# FEE_v0_3.net
KiCad netlist of a schematic drawn in EAGLE
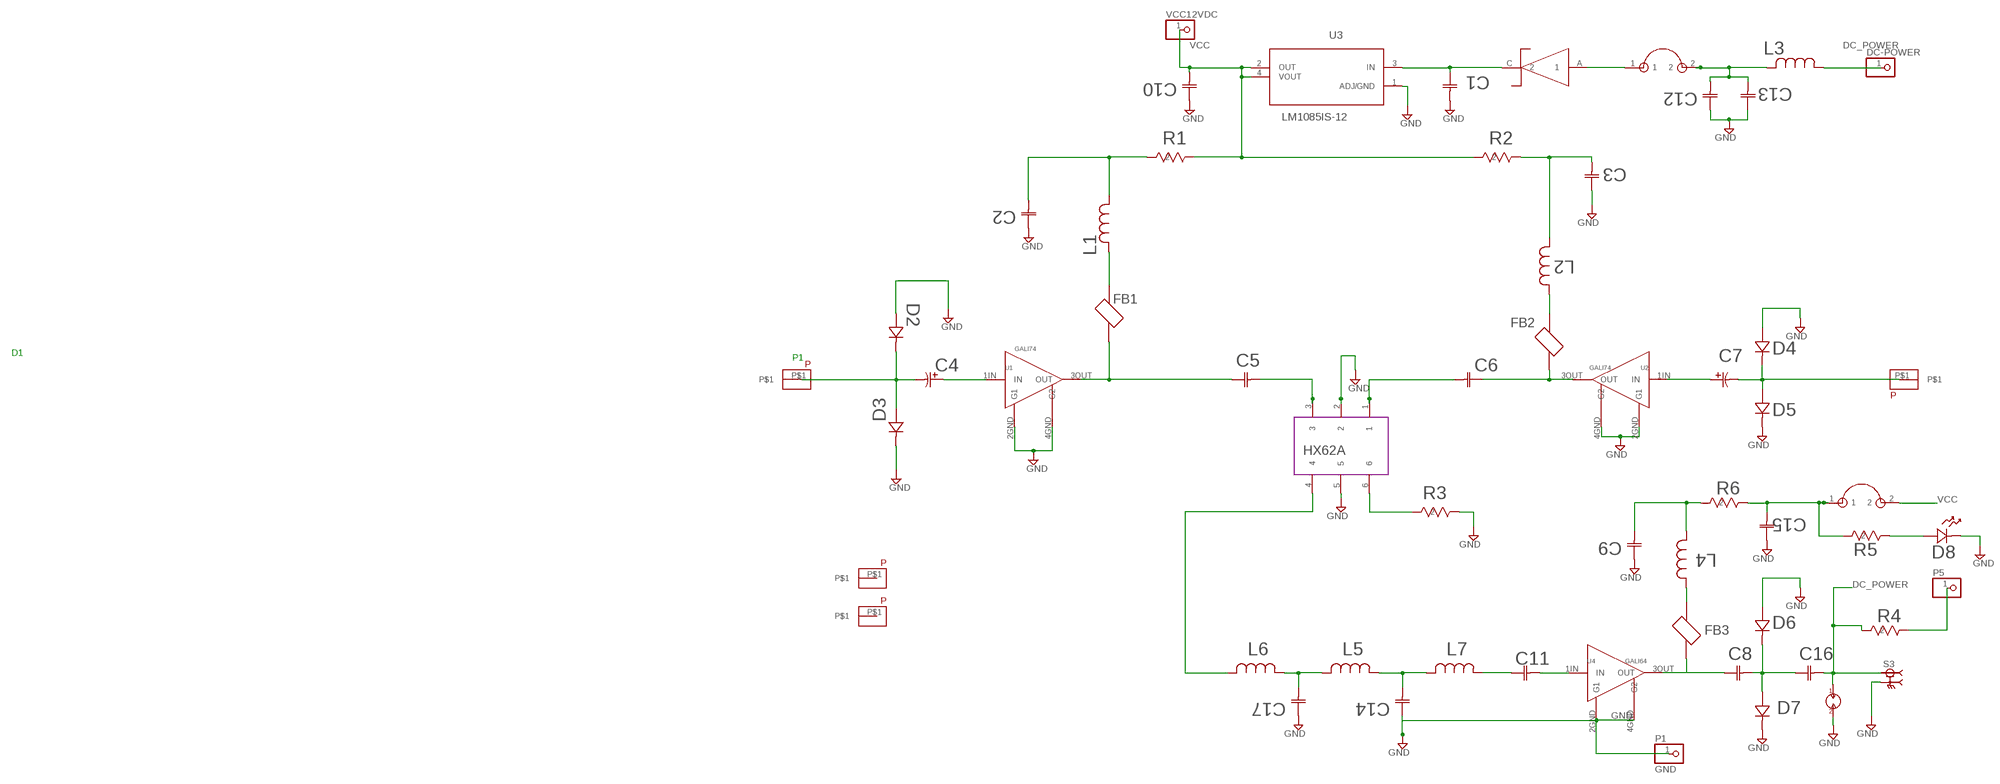
[diagram p0: schematic, sheet 1]

(export (version "E")
  (design (tool "Eeschema 10.0.6"))
  (components
    (comp (ref "C1")
      (value "F931E106MCC")
      (footprint "eagle-import:F93-C_AVX")
      (fields (field (name "COPYRIGHT") "Copyright (C) 2018 Accelerated Designs. All rights reserved"))
      (libsource (lib "eagle-import") (part "F931E106MCC"))
    )
    (comp (ref "C2")
      (value "C1206C104G5JAC7800")
      (footprint "eagle-import:CAPC340180_135N_KEM")
      (libsource (lib "eagle-import") (part "C1206C104G5JAC7800"))
    )
    (comp (ref "C3")
      (value "C1206C104G5JAC7800")
      (footprint "eagle-import:CAPC340180_135N_KEM")
      (libsource (lib "eagle-import") (part "C1206C104G5JAC7800"))
    )
    (comp (ref "C4")
      (value "ECJ-3FB2J102K")
      (footprint "eagle-import:CC1206_3_PAN")
      (libsource (lib "eagle-import") (part "ECJ-3FB2J102K"))
    )
    (comp (ref "C5")
      (value "C1206C104G5JAC7800")
      (footprint "eagle-import:CAPC340180_135N_KEM")
      (libsource (lib "eagle-import") (part "C1206C104G5JAC7800"))
    )
    (comp (ref "C6")
      (value "C1206C104G5JAC7800")
      (footprint "eagle-import:CAPC340180_135N_KEM")
      (libsource (lib "eagle-import") (part "C1206C104G5JAC7800"))
    )
    (comp (ref "C7")
      (value "ECJ-3FB2J102K")
      (footprint "eagle-import:CC1206_3_PAN")
      (libsource (lib "eagle-import") (part "ECJ-3FB2J102K"))
    )
    (comp (ref "C8")
      (value "C1206C104G5JAC7800")
      (footprint "eagle-import:CAPC340180_135N_KEM")
      (libsource (lib "eagle-import") (part "C1206C104G5JAC7800"))
    )
    (comp (ref "C9")
      (value "C1206C104G5JAC7800")
      (footprint "eagle-import:CAPC340180_135N_KEM")
      (libsource (lib "eagle-import") (part "C1206C104G5JAC7800"))
    )
    (comp (ref "C10")
      (value "F931E106MCC")
      (footprint "eagle-import:F93-C_AVX")
      (fields (field (name "COPYRIGHT") "Copyright (C) 2018 Accelerated Designs. All rights reserved"))
      (libsource (lib "eagle-import") (part "F931E106MCC"))
    )
    (comp (ref "C11")
      (value "C1206C104G5JAC7800")
      (footprint "eagle-import:CAPC340180_135N_KEM")
      (libsource (lib "eagle-import") (part "C1206C104G5JAC7800"))
    )
    (comp (ref "C12")
      (value "C1206C104G5JAC7800")
      (footprint "eagle-import:CAPC340180_135N_KEM")
      (libsource (lib "eagle-import") (part "C1206C104G5JAC7800"))
    )
    (comp (ref "C13")
      (value "C1206C104G5JAC7800")
      (footprint "eagle-import:CAPC340180_135N_KEM")
      (libsource (lib "eagle-import") (part "C1206C104G5JAC7800"))
    )
    (comp (ref "C14")
      (value "06031A330GAT2A")
      (footprint "eagle-import:CAP_0603G_AVX")
      (fields (field (name "COPYRIGHT") "Copyright (C) 2018 Accelerated Designs. All rights reserved"))
      (libsource (lib "eagle-import") (part "06031A330GAT2A"))
    )
    (comp (ref "C15")
      (value "C1206C104G5JAC7800")
      (footprint "eagle-import:CAPC340180_135N_KEM")
      (libsource (lib "eagle-import") (part "C1206C104G5JAC7800"))
    )
    (comp (ref "C16")
      (value "C1206C104G5JAC7800")
      (footprint "eagle-import:CAPC340180_135N_KEM")
      (libsource (lib "eagle-import") (part "C1206C104G5JAC7800"))
    )
    (comp (ref "C17")
      (value "06031A330GAT2A")
      (footprint "eagle-import:CAP_0603G_AVX")
      (fields (field (name "COPYRIGHT") "Copyright (C) 2018 Accelerated Designs. All rights reserved"))
      (libsource (lib "eagle-import") (part "06031A330GAT2A"))
    )
    (comp (ref "D1")
      (value "DIOM5436X247N")
      (footprint "eagle-import:DIOM5436X247N")
      (libsource (lib "eagle-import") (part "DIOM5436X247N"))
    )
    (comp (ref "D2")
      (value "1N4148WX-TP")
      (footprint "eagle-import:CR_SOD323_MCC")
      (fields (field (name "COPYRIGHT") "Copyright (C) 2018 Accelerated Designs. All rights reserved"))
      (libsource (lib "eagle-import") (part "1N4148WX-TP"))
    )
    (comp (ref "D3")
      (value "1N4148WX-TP")
      (footprint "eagle-import:CR_SOD323_MCC")
      (fields (field (name "COPYRIGHT") "Copyright (C) 2018 Accelerated Designs. All rights reserved"))
      (libsource (lib "eagle-import") (part "1N4148WX-TP"))
    )
    (comp (ref "D4")
      (value "1N4148WX-TP")
      (footprint "eagle-import:CR_SOD323_MCC")
      (fields (field (name "COPYRIGHT") "Copyright (C) 2018 Accelerated Designs. All rights reserved"))
      (libsource (lib "eagle-import") (part "1N4148WX-TP"))
    )
    (comp (ref "D5")
      (value "1N4148WX-TP")
      (footprint "eagle-import:CR_SOD323_MCC")
      (fields (field (name "COPYRIGHT") "Copyright (C) 2018 Accelerated Designs. All rights reserved"))
      (libsource (lib "eagle-import") (part "1N4148WX-TP"))
    )
    (comp (ref "D6")
      (value "1N4148WX-TP")
      (footprint "eagle-import:CR_SOD323_MCC")
      (fields (field (name "COPYRIGHT") "Copyright (C) 2018 Accelerated Designs. All rights reserved"))
      (libsource (lib "eagle-import") (part "1N4148WX-TP"))
    )
    (comp (ref "D7")
      (value "1N4148WX-TP")
      (footprint "eagle-import:CR_SOD323_MCC")
      (fields (field (name "COPYRIGHT") "Copyright (C) 2018 Accelerated Designs. All rights reserved"))
      (libsource (lib "eagle-import") (part "1N4148WX-TP"))
    )
    (comp (ref "D8")
      (value "SML-LX1206SIC-TR")
      (footprint "eagle-import:LED_SML-LX1206SIC-TR_LUM")
      (fields (field (name "COPYRIGHT") "Copyright (C) 2018 Accelerated Designs. All rights reserved"))
      (libsource (lib "eagle-import") (part "SML-LX1206SIC-TR"))
    )
    (comp (ref "DC-POWER")
      (value "PINHD-1X1")
      (footprint "eagle-import:1X01")
      (libsource (lib "eagle-import") (part "PINHD-1X1"))
    )
    (comp (ref "FB1")
      (value "HZ0805C202R-10")
      (footprint "eagle-import:FB_HZ0805C202R-10")
      (fields
        (field (name "DIGI-KEY_PART_NUMBER") "240-2396-1-ND")
        (field (name "MF") "Laird-Signal Integrity")
      )
      (libsource (lib "eagle-import") (part "HZ0805C202R-10"))
    )
    (comp (ref "FB2")
      (value "HZ0805C202R-10")
      (footprint "eagle-import:FB_HZ0805C202R-10")
      (fields
        (field (name "DIGI-KEY_PART_NUMBER") "240-2396-1-ND")
        (field (name "MF") "Laird-Signal Integrity")
      )
      (libsource (lib "eagle-import") (part "HZ0805C202R-10"))
    )
    (comp (ref "FB3")
      (value "HZ0805C202R-10")
      (footprint "eagle-import:FB_HZ0805C202R-10")
      (fields
        (field (name "DIGI-KEY_PART_NUMBER") "240-2396-1-ND")
        (field (name "MF") "Laird-Signal Integrity")
      )
      (libsource (lib "eagle-import") (part "HZ0805C202R-10"))
    )
    (comp (ref "L1")
      (value "AISC-1008-4R7J-T")
      (footprint "eagle-import:AISC-1008_ABR")
      (libsource (lib "eagle-import") (part "AISC-1008-4R7J-T"))
    )
    (comp (ref "L2")
      (value "AISC-1008-4R7J-T")
      (footprint "eagle-import:AISC-1008_ABR")
      (libsource (lib "eagle-import") (part "AISC-1008-4R7J-T"))
    )
    (comp (ref "L3")
      (value "AISC-1008-4R7J-T")
      (footprint "eagle-import:AISC-1008_ABR")
      (libsource (lib "eagle-import") (part "AISC-1008-4R7J-T"))
    )
    (comp (ref "L4")
      (value "AISC-1008-4R7J-T")
      (footprint "eagle-import:AISC-1008_ABR")
      (libsource (lib "eagle-import") (part "AISC-1008-4R7J-T"))
    )
    (comp (ref "L5")
      (value "AISC-1008-4R7J-T")
      (footprint "eagle-import:AISC-1008_ABR")
      (libsource (lib "eagle-import") (part "AISC-1008-4R7J-T"))
    )
    (comp (ref "L6")
      (value "AISC-1008-4R7J-T")
      (footprint "eagle-import:AISC-1008_ABR")
      (libsource (lib "eagle-import") (part "AISC-1008-4R7J-T"))
    )
    (comp (ref "L7")
      (value "AISC-1008-4R7J-T")
      (footprint "eagle-import:AISC-1008_ABR")
      (libsource (lib "eagle-import") (part "AISC-1008-4R7J-T"))
    )
    (comp (ref "P1")
      (value "GND")
      (footprint "eagle-import:1X01")
      (libsource (lib "eagle-import") (part "PINHD-1X1"))
    )
    (comp (ref "P5")
      (value "PINHD-1X1")
      (footprint "eagle-import:1X01")
      (libsource (lib "eagle-import") (part "PINHD-1X1"))
    )
    (comp (ref "R1")
      (value "ERJ-1TYJ910U")
      (footprint "eagle-import:RC2512N_PAN")
      (libsource (lib "eagle-import") (part "ERJ-1TYJ910U"))
    )
    (comp (ref "R2")
      (value "ERJ-1TYJ910U")
      (footprint "eagle-import:RC2512N_PAN")
      (libsource (lib "eagle-import") (part "ERJ-1TYJ910U"))
    )
    (comp (ref "R3")
      (value "ERJ-P08J510V")
      (footprint "eagle-import:RC1206N_PAN")
      (libsource (lib "eagle-import") (part "ERJ-P08J510V"))
    )
    (comp (ref "R4")
      (value "ERJ-8GEYJ472V")
      (footprint "eagle-import:RC1206N_PAN")
      (libsource (lib "eagle-import") (part "ERJ-8GEYJ472V"))
    )
    (comp (ref "R5")
      (value "ERJ-8GEYJ471V")
      (footprint "eagle-import:RC1206N_PAN")
      (libsource (lib "eagle-import") (part "ERJ-8GEYJ471V"))
    )
    (comp (ref "R6")
      (value "ERJ-1TNF95R3U")
      (footprint "eagle-import:RC2512N_PAN")
      (libsource (lib "eagle-import") (part "ERJ-1TNF95R3U"))
    )
    (comp (ref "S3")
      (value "142-0701-201")
      (footprint "eagle-import:JOHNSON_142-0701-201")
      (fields (field (name "MF") "Cinch Connectivity Solutions Johnson"))
      (libsource (lib "eagle-import") (part "142-0701-201"))
    )
    (comp (ref "U$1") (value "P") (footprint "eagle-import:P") (libsource (lib "eagle-import") (part "P")))
    (comp (ref "U$2") (value "P") (footprint "eagle-import:P") (libsource (lib "eagle-import") (part "P")))
    (comp (ref "U$3") (value "P") (footprint "eagle-import:P") (libsource (lib "eagle-import") (part "P")))
    (comp (ref "U$4") (value "P") (footprint "eagle-import:P") (libsource (lib "eagle-import") (part "P")))
    (comp (ref "U$5")
      (value "JMP1,JMP2")
      (footprint "eagle-import:JMP1,JMP2")
      (libsource (lib "eagle-import") (part "JMP1,JMP2"))
    )
    (comp (ref "U$6")
      (value "JMP1,JMP2")
      (footprint "eagle-import:JMP1,JMP2")
      (libsource (lib "eagle-import") (part "JMP1,JMP2"))
    )
    (comp (ref "U$7")
      (value "HX62A")
      (footprint "eagle-import:HX62A")
      (libsource (lib "eagle-import") (part "HX62A"))
    )
    (comp (ref "U$8")
      (value "GDTI")
      (footprint "eagle-import:GDTI")
      (libsource (lib "eagle-import") (part "GDTI"))
    )
    (comp (ref "U1")
      (value "GALI74")
      (footprint "eagle-import:DF782")
      (fields (field (name "MF") "Mini-Circuits") (field (name "MP") "GALI-74+"))
      (libsource (lib "eagle-import") (part "GALI74"))
    )
    (comp (ref "U2")
      (value "GALI74")
      (footprint "eagle-import:DF782")
      (fields (field (name "MF") "Mini-Circuits") (field (name "MP") "GALI-74+"))
      (libsource (lib "eagle-import") (part "GALI74"))
    )
    (comp (ref "U3")
      (value "LM1085IS-12")
      (footprint "eagle-import:TO254P1435X457-3N")
      (fields
        (field (name "DIGI-KEY_PART_NUMBER") "LM1085IS-12/NOPB-ND")
        (field (name "MF") "Texas Instruments")
      )
      (libsource (lib "eagle-import") (part "LM1085IS-12"))
    )
    (comp (ref "U4")
      (value "GALI64")
      (footprint "eagle-import:DF782")
      (fields (field (name "MF") "Mini-Circuits") (field (name "MP") "GALI-74+"))
      (libsource (lib "eagle-import") (part "GALI64"))
    )
    (comp (ref "VCC12VDC")
      (value "PINHD-1X1")
      (footprint "eagle-import:1X01")
      (libsource (lib "eagle-import") (part "PINHD-1X1"))
    )
  )
  (nets
    (net (code "1") (name "/DC_POWER") (class "Default")
      (node (ref "C16") (pin "2") (pinfunction "2_2") (pintype "passive"))
      (node (ref "DC-POWER") (pin "1") (pinfunction "1_1") (pintype "passive"))
      (node (ref "L3") (pin "1") (pinfunction "1_1") (pintype "passive"))
      (node (ref "R4") (pin "2") (pinfunction "2_2") (pintype "passive"))
      (node (ref "S3") (pin "1") (pinfunction "1_1") (pintype "passive"))
      (node (ref "U$8") (pin "1") (pinfunction "1_1") (pintype "bidirectional"))
    )
    (net (code "2") (name "/VCC") (class "Default")
      (node (ref "C10") (pin "2") (pinfunction "2_2") (pintype "passive"))
      (node (ref "R1") (pin "1") (pinfunction "1_1") (pintype "passive"))
      (node (ref "R2") (pin "2") (pinfunction "2_2") (pintype "passive"))
      (node (ref "U$6") (pin "2") (pinfunction "2_2") (pintype "bidirectional"))
      (node (ref "U3") (pin "2") (pinfunction "OUT_2") (pintype "output"))
      (node (ref "U3") (pin "4") (pinfunction "VOUT_4") (pintype "output"))
      (node (ref "VCC12VDC") (pin "1") (pinfunction "1_1") (pintype "passive"))
    )
    (net (code "3") (name "GND") (class "Default")
      (node (ref "C1") (pin "2") (pinfunction "2_2") (pintype "passive"))
      (node (ref "C10") (pin "1") (pinfunction "1_1") (pintype "passive"))
      (node (ref "C12") (pin "1") (pinfunction "1_1") (pintype "passive"))
      (node (ref "C13") (pin "1") (pinfunction "1_1") (pintype "passive"))
      (node (ref "C14") (pin "1") (pinfunction "1_1") (pintype "passive"))
      (node (ref "C15") (pin "1") (pinfunction "1_1") (pintype "passive"))
      (node (ref "C17") (pin "1") (pinfunction "1_1") (pintype "passive"))
      (node (ref "C2") (pin "1") (pinfunction "1_1") (pintype "passive"))
      (node (ref "C3") (pin "1") (pinfunction "1_1") (pintype "passive"))
      (node (ref "C9") (pin "1") (pinfunction "1_1") (pintype "passive"))
      (node (ref "D2") (pin "2") (pinfunction "2_2") (pintype "passive"))
      (node (ref "D3") (pin "1") (pinfunction "1_1") (pintype "passive"))
      (node (ref "D4") (pin "2") (pinfunction "2_2") (pintype "passive"))
      (node (ref "D5") (pin "1") (pinfunction "1_1") (pintype "passive"))
      (node (ref "D6") (pin "2") (pinfunction "2_2") (pintype "passive"))
      (node (ref "D7") (pin "1") (pinfunction "1_1") (pintype "passive"))
      (node (ref "D8") (pin "1") (pinfunction "1_1") (pintype "passive"))
      (node (ref "P1") (pin "1") (pinfunction "1_1") (pintype "passive"))
      (node (ref "R3") (pin "1") (pinfunction "1_1") (pintype "passive"))
      (node (ref "S3") (pin "2") (pinfunction "2_2") (pintype "passive"))
      (node (ref "S3") (pin "3") (pinfunction "2_3") (pintype "passive"))
      (node (ref "S3") (pin "4") (pinfunction "2_4") (pintype "passive"))
      (node (ref "S3") (pin "5") (pinfunction "2_5") (pintype "passive"))
      (node (ref "U$7") (pin "2") (pinfunction "2_2") (pintype "bidirectional"))
      (node (ref "U$7") (pin "5") (pinfunction "5_5") (pintype "bidirectional"))
      (node (ref "U$8") (pin "2") (pinfunction "2_2") (pintype "bidirectional"))
      (node (ref "U1") (pin "2GND") (pinfunction "G1_2GND") (pintype "power_in"))
      (node (ref "U1") (pin "4GND") (pinfunction "G2_4GND") (pintype "power_in"))
      (node (ref "U2") (pin "2GND") (pinfunction "G1_2GND") (pintype "power_in"))
      (node (ref "U2") (pin "4GND") (pinfunction "G2_4GND") (pintype "power_in"))
      (node (ref "U3") (pin "1") (pinfunction "ADJ/GND_1") (pintype "passive"))
      (node (ref "U4") (pin "2GND") (pinfunction "G1_2GND") (pintype "power_in"))
      (node (ref "U4") (pin "4GND") (pinfunction "G2_4GND") (pintype "power_in"))
    )
    (net (code "4") (name "Net-(C2-Pad2)") (class "Default")
      (node (ref "C2") (pin "2") (pinfunction "2_2") (pintype "passive"))
      (node (ref "L1") (pin "1") (pinfunction "1_1") (pintype "passive"))
      (node (ref "R1") (pin "2") (pinfunction "2_2") (pintype "passive"))
    )
    (net (code "5") (name "Net-(C3-Pad2)") (class "Default")
      (node (ref "C3") (pin "2") (pinfunction "2_2") (pintype "passive"))
      (node (ref "L2") (pin "1") (pinfunction "1_1") (pintype "passive"))
      (node (ref "R2") (pin "1") (pinfunction "1_1") (pintype "passive"))
    )
    (net (code "6") (name "Net-(C4-Pad2)") (class "Default")
      (node (ref "C4") (pin "2") (pinfunction "2_2") (pintype "passive"))
      (node (ref "D2") (pin "1") (pinfunction "1_1") (pintype "passive"))
      (node (ref "D3") (pin "2") (pinfunction "2_2") (pintype "passive"))
      (node (ref "U$1") (pin "P$1") (pinfunction "P$1_P$1") (pintype "bidirectional"))
    )
    (net (code "7") (name "Net-(C5-Pad2)") (class "Default")
      (node (ref "C5") (pin "2") (pinfunction "2_2") (pintype "passive"))
      (node (ref "U$7") (pin "3") (pinfunction "3_3") (pintype "bidirectional"))
    )
    (net (code "8") (name "Net-(C6-Pad2)") (class "Default")
      (node (ref "C6") (pin "2") (pinfunction "2_2") (pintype "passive"))
      (node (ref "U$7") (pin "1") (pinfunction "1_1") (pintype "bidirectional"))
    )
    (net (code "9") (name "Net-(C7-Pad2)") (class "Default")
      (node (ref "C7") (pin "2") (pinfunction "2_2") (pintype "passive"))
      (node (ref "D4") (pin "1") (pinfunction "1_1") (pintype "passive"))
      (node (ref "D5") (pin "2") (pinfunction "2_2") (pintype "passive"))
      (node (ref "U$2") (pin "P$1") (pinfunction "P$1_P$1") (pintype "bidirectional"))
    )
    (net (code "10") (name "Net-(C9-Pad2)") (class "Default")
      (node (ref "C9") (pin "2") (pinfunction "2_2") (pintype "passive"))
      (node (ref "L4") (pin "1") (pinfunction "1_1") (pintype "passive"))
      (node (ref "R6") (pin "2") (pinfunction "2_2") (pintype "passive"))
    )
    (net (code "11") (name "Net-(C11-Pad1)") (class "Default")
      (node (ref "C11") (pin "1") (pinfunction "1_1") (pintype "passive"))
      (node (ref "L7") (pin "1") (pinfunction "1_1") (pintype "passive"))
    )
    (net (code "12") (name "Net-(C12-Pad2)") (class "Default")
      (node (ref "C12") (pin "2") (pinfunction "2_2") (pintype "passive"))
      (node (ref "C13") (pin "2") (pinfunction "2_2") (pintype "passive"))
      (node (ref "L3") (pin "2") (pinfunction "2_2") (pintype "passive"))
      (node (ref "U$5") (pin "2") (pinfunction "2_2") (pintype "bidirectional"))
    )
    (net (code "13") (name "Net-(C14-Pad2)") (class "Default")
      (node (ref "C14") (pin "2") (pinfunction "2_2") (pintype "passive"))
      (node (ref "L5") (pin "1") (pinfunction "1_1") (pintype "passive"))
      (node (ref "L7") (pin "2") (pinfunction "2_2") (pintype "passive"))
    )
    (net (code "14") (name "Net-(C15-Pad2)") (class "Default")
      (node (ref "C15") (pin "2") (pinfunction "2_2") (pintype "passive"))
      (node (ref "R5") (pin "2") (pinfunction "2_2") (pintype "passive"))
      (node (ref "R6") (pin "1") (pinfunction "1_1") (pintype "passive"))
      (node (ref "U$6") (pin "1") (pinfunction "1_1") (pintype "bidirectional"))
    )
    (net (code "15") (name "Net-(C16-Pad1)") (class "Default")
      (node (ref "C16") (pin "1") (pinfunction "1_1") (pintype "passive"))
      (node (ref "C8") (pin "2") (pinfunction "2_2") (pintype "passive"))
      (node (ref "D6") (pin "1") (pinfunction "1_1") (pintype "passive"))
      (node (ref "D7") (pin "2") (pinfunction "2_2") (pintype "passive"))
    )
    (net (code "16") (name "Net-(C17-Pad2)") (class "Default")
      (node (ref "C17") (pin "2") (pinfunction "2_2") (pintype "passive"))
      (node (ref "L5") (pin "2") (pinfunction "2_2") (pintype "passive"))
      (node (ref "L6") (pin "1") (pinfunction "1_1") (pintype "passive"))
    )
    (net (code "17") (name "Net-(D1-1)") (class "Default")
      (node (ref "D1") (pin "A") (pinfunction "1_A") (pintype "bidirectional"))
      (node (ref "U$5") (pin "1") (pinfunction "1_1") (pintype "bidirectional"))
    )
    (net (code "18") (name "Net-(D1-2)") (class "Default")
      (node (ref "C1") (pin "1") (pinfunction "1_1") (pintype "passive"))
      (node (ref "D1") (pin "C") (pinfunction "2_C") (pintype "bidirectional"))
      (node (ref "U3") (pin "3") (pinfunction "IN_3") (pintype "power_in"))
    )
    (net (code "19") (name "Net-(D8-Pad2)") (class "Default")
      (node (ref "D8") (pin "2") (pinfunction "2_2") (pintype "passive"))
      (node (ref "R5") (pin "1") (pinfunction "1_1") (pintype "passive"))
    )
    (net (code "20") (name "Net-(FB1-Pad2)") (class "Default")
      (node (ref "FB1") (pin "2") (pinfunction "2_2") (pintype "passive"))
      (node (ref "L1") (pin "2") (pinfunction "2_2") (pintype "passive"))
    )
    (net (code "21") (name "Net-(FB2-Pad2)") (class "Default")
      (node (ref "FB2") (pin "2") (pinfunction "2_2") (pintype "passive"))
      (node (ref "L2") (pin "2") (pinfunction "2_2") (pintype "passive"))
    )
    (net (code "22") (name "Net-(FB3-Pad2)") (class "Default")
      (node (ref "FB3") (pin "2") (pinfunction "2_2") (pintype "passive"))
      (node (ref "L4") (pin "2") (pinfunction "2_2") (pintype "passive"))
    )
    (net (code "23") (name "Net-(L6-Pad2)") (class "Default")
      (node (ref "L6") (pin "2") (pinfunction "2_2") (pintype "passive"))
      (node (ref "U$7") (pin "4") (pinfunction "4_4") (pintype "bidirectional"))
    )
    (net (code "24") (name "Net-(P5-Pad1)") (class "Default")
      (node (ref "P5") (pin "1") (pinfunction "1_1") (pintype "passive"))
      (node (ref "R4") (pin "1") (pinfunction "1_1") (pintype "passive"))
    )
    (net (code "25") (name "Net-(R3-Pad2)") (class "Default")
      (node (ref "R3") (pin "2") (pinfunction "2_2") (pintype "passive"))
      (node (ref "U$7") (pin "6") (pinfunction "6_6") (pintype "bidirectional"))
    )
    (net (code "26") (name "Net-(U1-IN)") (class "Default")
      (node (ref "C4") (pin "1") (pinfunction "1_1") (pintype "passive"))
      (node (ref "U1") (pin "1IN") (pinfunction "IN_1IN") (pintype "input"))
    )
    (net (code "27") (name "Net-(U1-OUT)") (class "Default")
      (node (ref "C5") (pin "1") (pinfunction "1_1") (pintype "passive"))
      (node (ref "FB1") (pin "1") (pinfunction "1_1") (pintype "passive"))
      (node (ref "U1") (pin "3OUT") (pinfunction "OUT_3OUT") (pintype "output"))
    )
    (net (code "28") (name "Net-(U2-IN)") (class "Default")
      (node (ref "C7") (pin "1") (pinfunction "1_1") (pintype "passive"))
      (node (ref "U2") (pin "1IN") (pinfunction "IN_1IN") (pintype "input"))
    )
    (net (code "29") (name "Net-(U2-OUT)") (class "Default")
      (node (ref "C6") (pin "1") (pinfunction "1_1") (pintype "passive"))
      (node (ref "FB2") (pin "1") (pinfunction "1_1") (pintype "passive"))
      (node (ref "U2") (pin "3OUT") (pinfunction "OUT_3OUT") (pintype "output"))
    )
    (net (code "30") (name "Net-(U4-IN)") (class "Default")
      (node (ref "C11") (pin "2") (pinfunction "2_2") (pintype "passive"))
      (node (ref "U4") (pin "1IN") (pinfunction "IN_1IN") (pintype "input"))
    )
    (net (code "31") (name "Net-(U4-OUT)") (class "Default")
      (node (ref "C8") (pin "1") (pinfunction "1_1") (pintype "passive"))
      (node (ref "FB3") (pin "1") (pinfunction "1_1") (pintype "passive"))
      (node (ref "U4") (pin "3OUT") (pinfunction "OUT_3OUT") (pintype "output"))
    )
    (net (code "32") (name "unconnected-(U$3-PadP$1)") (class "Default")
      (node (ref "U$3") (pin "P$1") (pinfunction "P$1_P$1") (pintype "bidirectional"))
    )
    (net (code "33") (name "unconnected-(U$4-PadP$1)") (class "Default")
      (node (ref "U$4") (pin "P$1") (pinfunction "P$1_P$1") (pintype "bidirectional"))
    )
  )
)
